# gaspmask.net
KiCad netlist of a schematic drawn in EAGLE
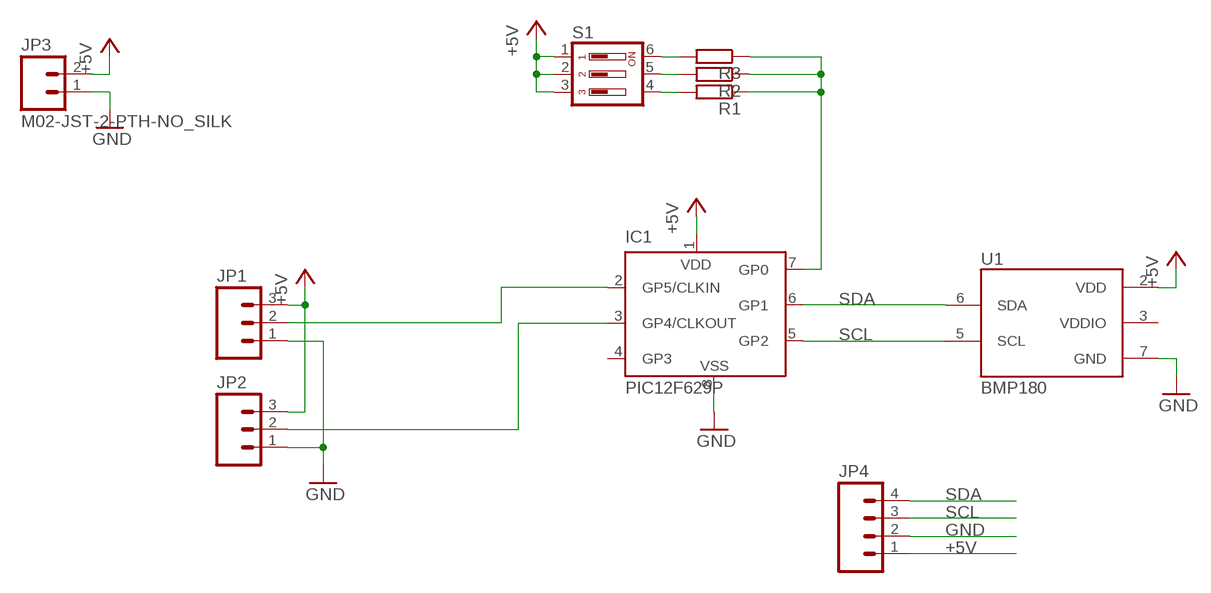
[diagram p0: schematic, sheet 1]

(export (version "E")
  (design (tool "Eeschema 10.0.6"))
  (components
    (comp (ref "IC1")
      (value "PIC12F629P")
      (footprint "eagle-import:DIL8")
      (libsource (lib "eagle-import") (part "PIC12F6P29"))
    )
    (comp (ref "JP1")
      (value "M03JST-PTH")
      (footprint "eagle-import:JST-3-PTH")
      (libsource (lib "eagle-import") (part "M03JST-PTH"))
    )
    (comp (ref "JP2")
      (value "M03JST-PTH")
      (footprint "eagle-import:JST-3-PTH")
      (libsource (lib "eagle-import") (part "M03JST-PTH"))
    )
    (comp (ref "JP3")
      (value "M02-JST-2-PTH-NO_SILK")
      (footprint "eagle-import:JST-2-PTH-NS")
      (libsource (lib "eagle-import") (part "M02-JST-2-PTH-NO_SILK"))
    )
    (comp (ref "JP4")
      (value "M04LOCK_LONGPADS")
      (footprint "eagle-import:1X04_LOCK_LONGPADS")
      (libsource (lib "eagle-import") (part "M04LOCK_LONGPADS"))
    )
    (comp (ref "R1")
      (value "R-EU_0204/7")
      (footprint "eagle-import:0204_7")
      (libsource (lib "eagle-import") (part "R-EU_0204/7"))
    )
    (comp (ref "R2")
      (value "R-EU_0204/7")
      (footprint "eagle-import:0204_7")
      (libsource (lib "eagle-import") (part "R-EU_0204/7"))
    )
    (comp (ref "R3")
      (value "R-EU_0204/7")
      (footprint "eagle-import:0204_7")
      (libsource (lib "eagle-import") (part "R-EU_0204/7"))
    )
    (comp (ref "S1")
      (value "DIP03YL")
      (footprint "eagle-import:DIP03YL")
      (libsource (lib "eagle-import") (part "DIP03YL"))
    )
    (comp (ref "U1")
      (value "BMP180")
      (footprint "eagle-import:BMP180")
      (libsource (lib "eagle-import") (part "BMP180"))
    )
  )
  (nets
    (net (code "1") (name "+5V") (class "Default")
      (node (ref "IC1") (pin "1") (pinfunction "VDD_1") (pintype "power_in"))
      (node (ref "JP1") (pin "3") (pinfunction "3_3") (pintype "passive"))
      (node (ref "JP2") (pin "3") (pinfunction "3_3") (pintype "passive"))
      (node (ref "JP3") (pin "2") (pinfunction "2_2") (pintype "passive"))
      (node (ref "JP4") (pin "1") (pinfunction "1_1") (pintype "passive"))
      (node (ref "S1") (pin "1") (pinfunction "1_1") (pintype "passive"))
      (node (ref "S1") (pin "2") (pinfunction "2_2") (pintype "passive"))
      (node (ref "S1") (pin "3") (pinfunction "3_3") (pintype "passive"))
      (node (ref "U1") (pin "2") (pinfunction "VDD_2") (pintype "power_in"))
    )
    (net (code "2") (name "/SCL") (class "Default")
      (node (ref "IC1") (pin "5") (pinfunction "GP2_5") (pintype "bidirectional"))
      (node (ref "JP4") (pin "3") (pinfunction "3_3") (pintype "passive"))
      (node (ref "U1") (pin "5") (pinfunction "SCL_5") (pintype "input"))
    )
    (net (code "3") (name "/SDA") (class "Default")
      (node (ref "IC1") (pin "6") (pinfunction "GP1_6") (pintype "bidirectional"))
      (node (ref "JP4") (pin "4") (pinfunction "4_4") (pintype "passive"))
      (node (ref "U1") (pin "6") (pinfunction "SDA_6") (pintype "bidirectional"))
    )
    (net (code "4") (name "/VDDIO") (class "Default")
      (node (ref "U1") (pin "3") (pinfunction "VDDIO_3") (pintype "power_in"))
    )
    (net (code "5") (name "GND") (class "Default")
      (node (ref "IC1") (pin "8") (pinfunction "VSS_8") (pintype "power_in"))
      (node (ref "JP1") (pin "1") (pinfunction "1_1") (pintype "passive"))
      (node (ref "JP2") (pin "1") (pinfunction "1_1") (pintype "passive"))
      (node (ref "JP3") (pin "1") (pinfunction "1_1") (pintype "passive"))
      (node (ref "JP4") (pin "2") (pinfunction "2_2") (pintype "passive"))
      (node (ref "U1") (pin "7") (pinfunction "GND_7") (pintype "power_in"))
    )
    (net (code "6") (name "Net-(IC1-GP0)") (class "Default")
      (node (ref "IC1") (pin "7") (pinfunction "GP0_7") (pintype "bidirectional"))
      (node (ref "R1") (pin "1") (pinfunction "1_1") (pintype "passive"))
      (node (ref "R2") (pin "1") (pinfunction "1_1") (pintype "passive"))
      (node (ref "R3") (pin "1") (pinfunction "1_1") (pintype "passive"))
    )
    (net (code "7") (name "Net-(IC1-GP4{slash}CLKOUT)") (class "Default")
      (node (ref "IC1") (pin "3") (pinfunction "GP4/CLKOUT_3") (pintype "bidirectional"))
      (node (ref "JP2") (pin "2") (pinfunction "2_2") (pintype "passive"))
    )
    (net (code "8") (name "Net-(IC1-GP5{slash}CLKIN)") (class "Default")
      (node (ref "IC1") (pin "2") (pinfunction "GP5/CLKIN_2") (pintype "bidirectional"))
      (node (ref "JP1") (pin "2") (pinfunction "2_2") (pintype "passive"))
    )
    (net (code "9") (name "Net-(R1-Pad2)") (class "Default")
      (node (ref "R1") (pin "2") (pinfunction "2_2") (pintype "passive"))
      (node (ref "S1") (pin "4") (pinfunction "4_4") (pintype "passive"))
    )
    (net (code "10") (name "Net-(R2-Pad2)") (class "Default")
      (node (ref "R2") (pin "2") (pinfunction "2_2") (pintype "passive"))
      (node (ref "S1") (pin "5") (pinfunction "5_5") (pintype "passive"))
    )
    (net (code "11") (name "Net-(R3-Pad2)") (class "Default")
      (node (ref "R3") (pin "2") (pinfunction "2_2") (pintype "passive"))
      (node (ref "S1") (pin "6") (pinfunction "6_6") (pintype "passive"))
    )
    (net (code "12") (name "unconnected-(IC1-GP3-Pad4)") (class "Default")
      (node (ref "IC1") (pin "4") (pinfunction "GP3_4") (pintype "input"))
    )
  )
)
